# rsx_low_power_board_24V.net
KiCad netlist of a schematic drawn in Altium Designer
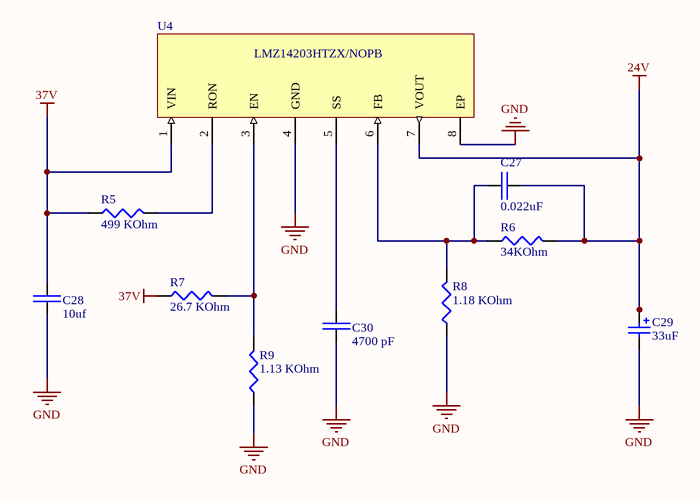
[diagram p0: rsx_low_power_board_24V.SchDoc]

(export (version "E")
  (design (tool "Eeschema 10.0.6"))
  (components
    (comp (ref "C27")
      (value "0.022uF")
      (footprint "0.022uF Ceramic")
      (description "KEMET - C0805C223K5RACTU - CAP, MLCC, X7R, 22NF, 50V, 0805")
      (fields (field (name "TOLERANCE") "10%") (field (name "VOLTAGE") "50V"))
      (libsource (lib "RSX_Capacitors") (part "0.022uF C0805C223K5RACTU"))
    )
    (comp (ref "C28")
      (value "10uf")
      (footprint "10uF capacitor LPB")
      (description "CAP CER 10UF 50V X5R 1206")
      (fields (field (name "TOLERANCE") "20%"))
      (libsource (lib "RSX_Capacitors") (part "GRT31CR61H106ME01L"))
    )
    (comp (ref "C29")
      (value "33uF")
      (footprint "33uF Through hole Radical")
      (description "CAP ALUM 33UF 20% 50V RADIAL")
      (fields (field (name "TOLERANCE") "20%"))
      (libsource (lib "RSX_Capacitors") (part "33uF UFW1H330MDD1TD"))
    )
    (comp (ref "C30")
      (value "4700 pF")
      (footprint "4700uF 0805")
      (description "KEMET - C0805C472K5RACTU - CERAMIC CAPACITOR 4700PF, 50V, X7R, 10%, 0805")
      (fields (field (name "TOLERANCE") "10%") (field (name "VOLTAGE") "50V"))
      (libsource (lib "RSX_Capacitors") (part "4700pF 0805"))
    )
    (comp (ref "R5")
      (value "499 KOhm")
      (footprint "499KOhm RG2012")
      (description "RES SMD 499K OHM 0.1% 1/8W 0805")
      (fields (field (name "TOLERANCE") "0.1%"))
      (libsource (lib "RSX_Resistors") (part "RG2012P-4993-B-T5"))
    )
    (comp (ref "R6")
      (value "34KOhm")
      (footprint "34 KOhm Resistor ERA-6A")
      (description "RES SMD 34K OHM 0.1% 1/8W 0805")
      (fields (field (name "TOLERANCE") "0.1%"))
      (libsource (lib "RSX_Resistors") (part "ERA6AEB3402V"))
    )
    (comp (ref "R7")
      (value "26.7 KOhm")
      (footprint "34 KOhm Resistor ERA-6A")
      (description "RES SMD 1.18K OHM 0.1% 1/8W 0805")
      (fields (field (name "TOLERANCE") "0.1%"))
      (libsource (lib "RSX_Resistors") (part "ERA-6AEB1181V"))
    )
    (comp (ref "R8")
      (value "1.18 KOhm")
      (footprint "34 KOhm Resistor ERA-6A")
      (description "RES SMD 1.18K OHM 0.1% 1/8W 0805")
      (fields (field (name "TOLERANCE") "0.1%"))
      (libsource (lib "RSX_Resistors") (part "ERA-6AEB1181V"))
    )
    (comp (ref "R9")
      (value "1.13 KOhm")
      (footprint "34 KOhm Resistor ERA-6A")
      (description "RES SMD 1.18K OHM 0.1% 1/8W 0805")
      (fields (field (name "TOLERANCE") "0.1%"))
      (libsource (lib "RSX_Resistors") (part "ERA-6AEB1181V"))
    )
    (comp (ref "U4")
      (value "LMZ14203HTZX/NOPB")
      (footprint "24V DC to DC buck")
      (description "IC BUCK SYNC ADJ 3A TO-PMOD-7")
      (libsource (lib "RSX_ICs") (part "LMZ14203HTZX/NOPB"))
    )
  )
  (nets
    (net (code "1") (name "24V") (class "Default")
      (node (ref "C27") (pin "2") (pinfunction "16_2") (pintype "passive"))
      (node (ref "C29") (pin "1") (pinfunction "1_1") (pintype "passive"))
      (node (ref "R6") (pin "2") (pinfunction "12_2") (pintype "passive"))
      (node (ref "U4") (pin "7") (pinfunction "VOUT_7") (pintype "output"))
    )
    (net (code "2") (name "37V") (class "Default")
      (node (ref "C28") (pin "1") (pinfunction "15_1") (pintype "passive"))
      (node (ref "R5") (pin "1") (pinfunction "11_1") (pintype "passive"))
      (node (ref "R7") (pin "1") (pinfunction "11_1") (pintype "passive"))
      (node (ref "U4") (pin "1") (pinfunction "VIN_1") (pintype "input"))
    )
    (net (code "3") (name "GND") (class "Default")
      (node (ref "C28") (pin "2") (pinfunction "16_2") (pintype "passive"))
      (node (ref "C29") (pin "2") (pinfunction "2_2") (pintype "passive"))
      (node (ref "C30") (pin "1") (pinfunction "15_1") (pintype "passive"))
      (node (ref "R8") (pin "1") (pinfunction "11_1") (pintype "passive"))
      (node (ref "R9") (pin "1") (pinfunction "11_1") (pintype "passive"))
      (node (ref "U4") (pin "4") (pinfunction "GND_4") (pintype "power_in"))
      (node (ref "U4") (pin "8") (pinfunction "EP_8") (pintype "passive"))
    )
    (net (code "4") (name "Net-(C27-15)") (class "Default")
      (node (ref "C27") (pin "1") (pinfunction "15_1") (pintype "passive"))
      (node (ref "R6") (pin "1") (pinfunction "11_1") (pintype "passive"))
      (node (ref "R8") (pin "2") (pinfunction "12_2") (pintype "passive"))
      (node (ref "U4") (pin "6") (pinfunction "FB_6") (pintype "input"))
    )
    (net (code "5") (name "Net-(C30-16)") (class "Default")
      (node (ref "C30") (pin "2") (pinfunction "16_2") (pintype "passive"))
      (node (ref "U4") (pin "5") (pinfunction "SS_5") (pintype "passive"))
    )
    (net (code "6") (name "Net-(R5-12)") (class "Default")
      (node (ref "R5") (pin "2") (pinfunction "12_2") (pintype "passive"))
      (node (ref "U4") (pin "2") (pinfunction "RON_2") (pintype "passive"))
    )
    (net (code "7") (name "Net-(R7-12)") (class "Default")
      (node (ref "R7") (pin "2") (pinfunction "12_2") (pintype "passive"))
      (node (ref "R9") (pin "2") (pinfunction "12_2") (pintype "passive"))
      (node (ref "U4") (pin "3") (pinfunction "EN_3") (pintype "input"))
    )
  )
)
